# reg.net
KiCad netlist of a schematic drawn in EAGLE
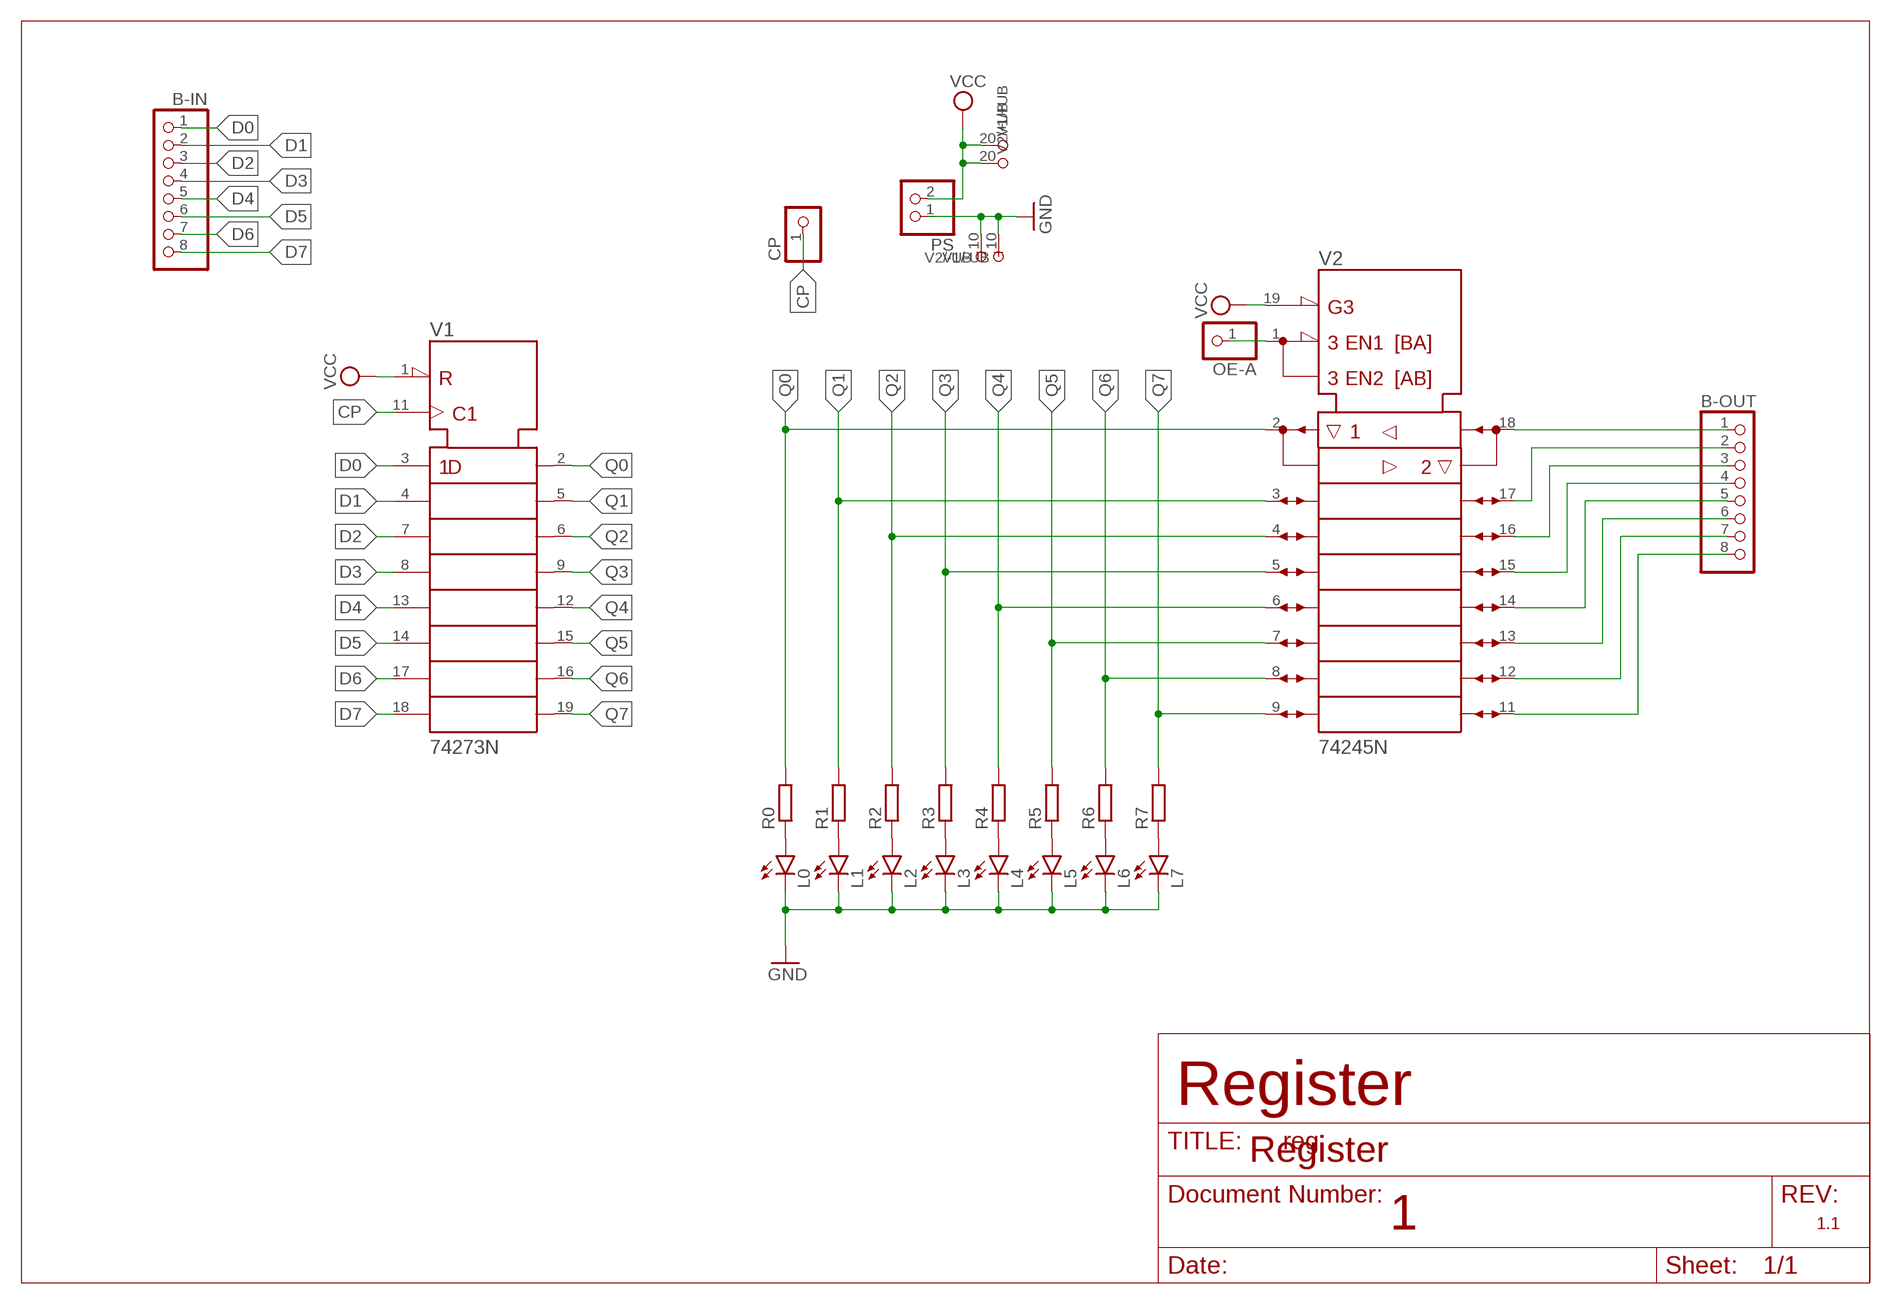
[diagram p0: schematic, sheet 1]

(export (version "E")
  (design (tool "Eeschema 10.0.6"))
  (components
    (comp (ref "B-IN")
      (value "PINHD-1X8")
      (footprint "eagle-import:1X08")
      (libsource (lib "eagle-import") (part "PINHD-1X8"))
    )
    (comp (ref "B-OUT")
      (value "PINHD-1X8")
      (footprint "eagle-import:1X08")
      (libsource (lib "eagle-import") (part "PINHD-1X8"))
    )
    (comp (ref "CP")
      (value "PINHD-1X1")
      (footprint "eagle-import:1X01")
      (libsource (lib "eagle-import") (part "PINHD-1X1"))
    )
    (comp (ref "L0")
      (value "LED5MM")
      (footprint "eagle-import:LED5MM")
      (libsource (lib "eagle-import") (part "LED5MM"))
    )
    (comp (ref "L1")
      (value "LED5MM")
      (footprint "eagle-import:LED5MM")
      (libsource (lib "eagle-import") (part "LED5MM"))
    )
    (comp (ref "L2")
      (value "LED5MM")
      (footprint "eagle-import:LED5MM")
      (libsource (lib "eagle-import") (part "LED5MM"))
    )
    (comp (ref "L3")
      (value "LED5MM")
      (footprint "eagle-import:LED5MM")
      (libsource (lib "eagle-import") (part "LED5MM"))
    )
    (comp (ref "L4")
      (value "LED5MM")
      (footprint "eagle-import:LED5MM")
      (libsource (lib "eagle-import") (part "LED5MM"))
    )
    (comp (ref "L5")
      (value "LED5MM")
      (footprint "eagle-import:LED5MM")
      (libsource (lib "eagle-import") (part "LED5MM"))
    )
    (comp (ref "L6")
      (value "LED5MM")
      (footprint "eagle-import:LED5MM")
      (libsource (lib "eagle-import") (part "LED5MM"))
    )
    (comp (ref "L7")
      (value "LED5MM")
      (footprint "eagle-import:LED5MM")
      (libsource (lib "eagle-import") (part "LED5MM"))
    )
    (comp (ref "OE-A")
      (value "PINHD-1X1")
      (footprint "eagle-import:1X01")
      (libsource (lib "eagle-import") (part "PINHD-1X1"))
    )
    (comp (ref "PS")
      (value "PINHD-1X2")
      (footprint "eagle-import:1X02")
      (libsource (lib "eagle-import") (part "PINHD-1X2"))
    )
    (comp (ref "R0")
      (value "R-EU_0204/7")
      (footprint "eagle-import:0204_7")
      (libsource (lib "eagle-import") (part "R-EU_0204/7"))
    )
    (comp (ref "R1")
      (value "R-EU_0204/7")
      (footprint "eagle-import:0204_7")
      (libsource (lib "eagle-import") (part "R-EU_0204/7"))
    )
    (comp (ref "R2")
      (value "R-EU_0204/7")
      (footprint "eagle-import:0204_7")
      (libsource (lib "eagle-import") (part "R-EU_0204/7"))
    )
    (comp (ref "R3")
      (value "R-EU_0204/7")
      (footprint "eagle-import:0204_7")
      (libsource (lib "eagle-import") (part "R-EU_0204/7"))
    )
    (comp (ref "R4")
      (value "R-EU_0204/7")
      (footprint "eagle-import:0204_7")
      (libsource (lib "eagle-import") (part "R-EU_0204/7"))
    )
    (comp (ref "R5")
      (value "R-EU_0204/7")
      (footprint "eagle-import:0204_7")
      (libsource (lib "eagle-import") (part "R-EU_0204/7"))
    )
    (comp (ref "R6")
      (value "R-EU_0204/7")
      (footprint "eagle-import:0204_7")
      (libsource (lib "eagle-import") (part "R-EU_0204/7"))
    )
    (comp (ref "R7")
      (value "R-EU_0204/7")
      (footprint "eagle-import:0204_7")
      (libsource (lib "eagle-import") (part "R-EU_0204/7"))
    )
    (comp (ref "V1")
      (value "74273N")
      (footprint "eagle-import:DIL20")
      (libsource (lib "eagle-import") (part "74273N"))
    )
    (comp (ref "V2")
      (value "74245N")
      (footprint "eagle-import:DIL20")
      (libsource (lib "eagle-import") (part "74245N"))
    )
  )
  (nets
    (net (code "1") (name "CP") (class "Default")
      (node (ref "CP") (pin "1") (pinfunction "1_1") (pintype "passive"))
      (node (ref "V1") (pin "11") (pinfunction "CLK_11") (pintype "input"))
    )
    (net (code "2") (name "D0") (class "Default")
      (node (ref "B-IN") (pin "1") (pinfunction "1_1") (pintype "passive"))
      (node (ref "V1") (pin "3") (pinfunction "1D_3") (pintype "input"))
    )
    (net (code "3") (name "D1") (class "Default")
      (node (ref "B-IN") (pin "2") (pinfunction "2_2") (pintype "passive"))
      (node (ref "V1") (pin "4") (pinfunction "2D_4") (pintype "input"))
    )
    (net (code "4") (name "D2") (class "Default")
      (node (ref "B-IN") (pin "3") (pinfunction "3_3") (pintype "passive"))
      (node (ref "V1") (pin "7") (pinfunction "3D_7") (pintype "input"))
    )
    (net (code "5") (name "D3") (class "Default")
      (node (ref "B-IN") (pin "4") (pinfunction "4_4") (pintype "passive"))
      (node (ref "V1") (pin "8") (pinfunction "4D_8") (pintype "input"))
    )
    (net (code "6") (name "D4") (class "Default")
      (node (ref "B-IN") (pin "5") (pinfunction "5_5") (pintype "passive"))
      (node (ref "V1") (pin "13") (pinfunction "5D_13") (pintype "input"))
    )
    (net (code "7") (name "D5") (class "Default")
      (node (ref "B-IN") (pin "6") (pinfunction "6_6") (pintype "passive"))
      (node (ref "V1") (pin "14") (pinfunction "6D_14") (pintype "input"))
    )
    (net (code "8") (name "D6") (class "Default")
      (node (ref "B-IN") (pin "7") (pinfunction "7_7") (pintype "passive"))
      (node (ref "V1") (pin "17") (pinfunction "7D_17") (pintype "input"))
    )
    (net (code "9") (name "D7") (class "Default")
      (node (ref "B-IN") (pin "8") (pinfunction "8_8") (pintype "passive"))
      (node (ref "V1") (pin "18") (pinfunction "8D_18") (pintype "input"))
    )
    (net (code "10") (name "GND") (class "Default")
      (node (ref "L0") (pin "K") (pinfunction "C_K") (pintype "passive"))
      (node (ref "L1") (pin "K") (pinfunction "C_K") (pintype "passive"))
      (node (ref "L2") (pin "K") (pinfunction "C_K") (pintype "passive"))
      (node (ref "L3") (pin "K") (pinfunction "C_K") (pintype "passive"))
      (node (ref "L4") (pin "K") (pinfunction "C_K") (pintype "passive"))
      (node (ref "L5") (pin "K") (pinfunction "C_K") (pintype "passive"))
      (node (ref "L6") (pin "K") (pinfunction "C_K") (pintype "passive"))
      (node (ref "L7") (pin "K") (pinfunction "C_K") (pintype "passive"))
      (node (ref "PS") (pin "1") (pinfunction "1_1") (pintype "passive"))
      (node (ref "V1") (pin "10") (pinfunction "-UB_10") (pintype "power_in"))
      (node (ref "V2") (pin "10") (pinfunction "-UB_10") (pintype "power_in"))
    )
    (net (code "11") (name "Net-(L0-PadA)") (class "Default")
      (node (ref "L0") (pin "A") (pinfunction "A_A") (pintype "passive"))
      (node (ref "R0") (pin "1") (pinfunction "1_1") (pintype "passive"))
    )
    (net (code "12") (name "Net-(L1-PadA)") (class "Default")
      (node (ref "L1") (pin "A") (pinfunction "A_A") (pintype "passive"))
      (node (ref "R1") (pin "1") (pinfunction "1_1") (pintype "passive"))
    )
    (net (code "13") (name "Net-(L2-PadA)") (class "Default")
      (node (ref "L2") (pin "A") (pinfunction "A_A") (pintype "passive"))
      (node (ref "R2") (pin "1") (pinfunction "1_1") (pintype "passive"))
    )
    (net (code "14") (name "Net-(L3-PadA)") (class "Default")
      (node (ref "L3") (pin "A") (pinfunction "A_A") (pintype "passive"))
      (node (ref "R3") (pin "1") (pinfunction "1_1") (pintype "passive"))
    )
    (net (code "15") (name "Net-(L4-PadA)") (class "Default")
      (node (ref "L4") (pin "A") (pinfunction "A_A") (pintype "passive"))
      (node (ref "R4") (pin "1") (pinfunction "1_1") (pintype "passive"))
    )
    (net (code "16") (name "Net-(L5-PadA)") (class "Default")
      (node (ref "L5") (pin "A") (pinfunction "A_A") (pintype "passive"))
      (node (ref "R5") (pin "1") (pinfunction "1_1") (pintype "passive"))
    )
    (net (code "17") (name "Net-(L6-PadA)") (class "Default")
      (node (ref "L6") (pin "A") (pinfunction "A_A") (pintype "passive"))
      (node (ref "R6") (pin "1") (pinfunction "1_1") (pintype "passive"))
    )
    (net (code "18") (name "Net-(L7-PadA)") (class "Default")
      (node (ref "L7") (pin "A") (pinfunction "A_A") (pintype "passive"))
      (node (ref "R7") (pin "1") (pinfunction "1_1") (pintype "passive"))
    )
    (net (code "19") (name "Net-(V2C-B1)") (class "Default")
      (node (ref "B-OUT") (pin "1") (pinfunction "1_1") (pintype "passive"))
      (node (ref "V2") (pin "18") (pinfunction "B1_18") (pintype "bidirectional"))
    )
    (net (code "20") (name "Net-(V2C-B2)") (class "Default")
      (node (ref "B-OUT") (pin "2") (pinfunction "2_2") (pintype "passive"))
      (node (ref "V2") (pin "17") (pinfunction "B2_17") (pintype "bidirectional"))
    )
    (net (code "21") (name "Net-(V2C-B3)") (class "Default")
      (node (ref "B-OUT") (pin "3") (pinfunction "3_3") (pintype "passive"))
      (node (ref "V2") (pin "16") (pinfunction "B3_16") (pintype "bidirectional"))
    )
    (net (code "22") (name "Net-(V2C-B4)") (class "Default")
      (node (ref "B-OUT") (pin "4") (pinfunction "4_4") (pintype "passive"))
      (node (ref "V2") (pin "15") (pinfunction "B4_15") (pintype "bidirectional"))
    )
    (net (code "23") (name "Net-(V2C-B5)") (class "Default")
      (node (ref "B-OUT") (pin "5") (pinfunction "5_5") (pintype "passive"))
      (node (ref "V2") (pin "14") (pinfunction "B5_14") (pintype "bidirectional"))
    )
    (net (code "24") (name "Net-(V2C-B6)") (class "Default")
      (node (ref "B-OUT") (pin "6") (pinfunction "6_6") (pintype "passive"))
      (node (ref "V2") (pin "13") (pinfunction "B6_13") (pintype "bidirectional"))
    )
    (net (code "25") (name "Net-(V2C-B7)") (class "Default")
      (node (ref "B-OUT") (pin "7") (pinfunction "7_7") (pintype "passive"))
      (node (ref "V2") (pin "12") (pinfunction "B7_12") (pintype "bidirectional"))
    )
    (net (code "26") (name "Net-(V2C-B8)") (class "Default")
      (node (ref "B-OUT") (pin "8") (pinfunction "8_8") (pintype "passive"))
      (node (ref "V2") (pin "11") (pinfunction "B8_11") (pintype "bidirectional"))
    )
    (net (code "27") (name "Net-(V2C-DIR)") (class "Default")
      (node (ref "OE-A") (pin "1") (pinfunction "1_1") (pintype "passive"))
      (node (ref "V2") (pin "1") (pinfunction "DIR_1") (pintype "input"))
    )
    (net (code "28") (name "Q0") (class "Default")
      (node (ref "R0") (pin "2") (pinfunction "2_2") (pintype "passive"))
      (node (ref "V1") (pin "2") (pinfunction "1Q_2") (pintype "output"))
      (node (ref "V2") (pin "2") (pinfunction "A1_2") (pintype "bidirectional"))
    )
    (net (code "29") (name "Q1") (class "Default")
      (node (ref "R1") (pin "2") (pinfunction "2_2") (pintype "passive"))
      (node (ref "V1") (pin "5") (pinfunction "2Q_5") (pintype "output"))
      (node (ref "V2") (pin "3") (pinfunction "A2_3") (pintype "bidirectional"))
    )
    (net (code "30") (name "Q2") (class "Default")
      (node (ref "R2") (pin "2") (pinfunction "2_2") (pintype "passive"))
      (node (ref "V1") (pin "6") (pinfunction "3Q_6") (pintype "output"))
      (node (ref "V2") (pin "4") (pinfunction "A3_4") (pintype "bidirectional"))
    )
    (net (code "31") (name "Q3") (class "Default")
      (node (ref "R3") (pin "2") (pinfunction "2_2") (pintype "passive"))
      (node (ref "V1") (pin "9") (pinfunction "4Q_9") (pintype "output"))
      (node (ref "V2") (pin "5") (pinfunction "A4_5") (pintype "bidirectional"))
    )
    (net (code "32") (name "Q4") (class "Default")
      (node (ref "R4") (pin "2") (pinfunction "2_2") (pintype "passive"))
      (node (ref "V1") (pin "12") (pinfunction "5Q_12") (pintype "output"))
      (node (ref "V2") (pin "6") (pinfunction "A5_6") (pintype "bidirectional"))
    )
    (net (code "33") (name "Q5") (class "Default")
      (node (ref "R5") (pin "2") (pinfunction "2_2") (pintype "passive"))
      (node (ref "V1") (pin "15") (pinfunction "6Q_15") (pintype "output"))
      (node (ref "V2") (pin "7") (pinfunction "A6_7") (pintype "bidirectional"))
    )
    (net (code "34") (name "Q6") (class "Default")
      (node (ref "R6") (pin "2") (pinfunction "2_2") (pintype "passive"))
      (node (ref "V1") (pin "16") (pinfunction "7Q_16") (pintype "output"))
      (node (ref "V2") (pin "8") (pinfunction "A7_8") (pintype "bidirectional"))
    )
    (net (code "35") (name "Q7") (class "Default")
      (node (ref "R7") (pin "2") (pinfunction "2_2") (pintype "passive"))
      (node (ref "V1") (pin "19") (pinfunction "8Q_19") (pintype "output"))
      (node (ref "V2") (pin "9") (pinfunction "A8_9") (pintype "bidirectional"))
    )
    (net (code "36") (name "VCC") (class "Default")
      (node (ref "PS") (pin "2") (pinfunction "2_2") (pintype "passive"))
      (node (ref "V1") (pin "1") (pinfunction "~{CLR}_1") (pintype "input"))
      (node (ref "V1") (pin "20") (pinfunction "+UB_20") (pintype "power_in"))
      (node (ref "V2") (pin "19") (pinfunction "~{G}_19") (pintype "input"))
      (node (ref "V2") (pin "20") (pinfunction "+UB_20") (pintype "power_in"))
    )
  )
)
